# FanPump.net
KiCad netlist of a schematic drawn in Altium Designer
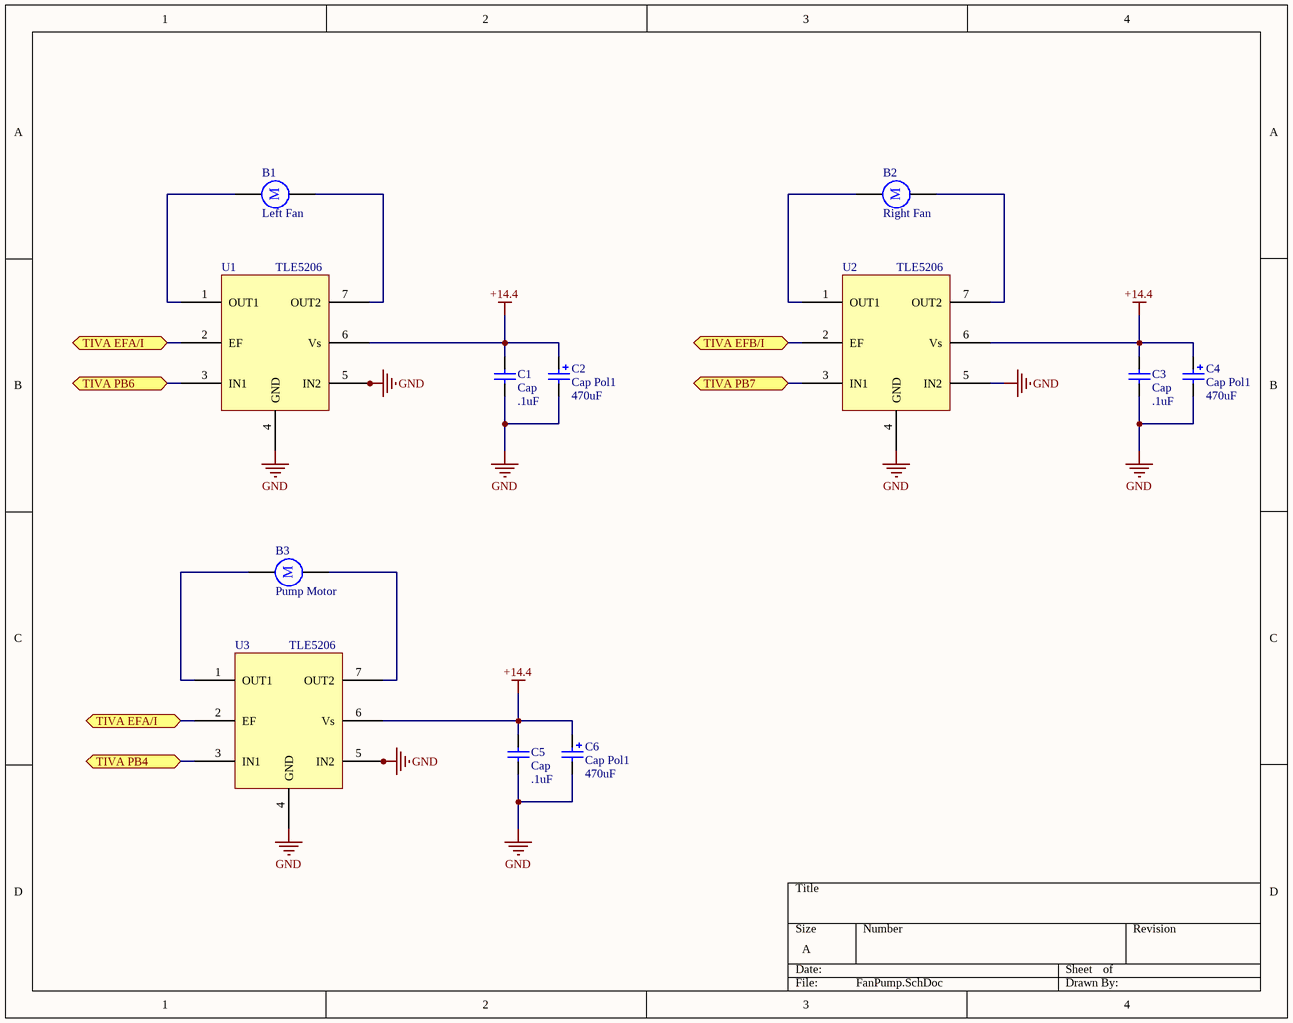
[diagram p0: FanPump.SchDoc]

(export (version "E")
  (design (tool "Eeschema 10.0.6"))
  (components
    (comp (ref "B1")
      (value "Left Fan")
      (footprint "RB5-10.5")
      (description "Motor, General Kind")
      (fields (field (name "MANUFACTURER") "Generic Components"))
      (libsource (lib "ME218_BaseLib") (part "Motor"))
    )
    (comp (ref "B2")
      (value "Right Fan")
      (footprint "RB5-10.5")
      (description "Motor, General Kind")
      (fields (field (name "MANUFACTURER") "Generic Components"))
      (libsource (lib "ME218_BaseLib") (part "Motor"))
    )
    (comp (ref "B3")
      (value "Pump Motor")
      (footprint "RB5-10.5")
      (description "Motor, General Kind")
      (fields (field (name "MANUFACTURER") "Generic Components"))
      (libsource (lib "ME218_BaseLib") (part "Motor"))
    )
    (comp (ref "C1")
      (value "Cap")
      (footprint "RAD-0.3")
      (description "Capacitor")
      (fields
        (field (name "MANUFACTURER") "Generic Components")
        (field (name "ALTIUM_VALUE") ".1uF")
        (field (name "PUBLISHER") "Altium Hobart Technology Centre")
      )
      (libsource (lib "ME218_BaseLib") (part "Cap"))
    )
    (comp (ref "C2")
      (value "Cap Pol1")
      (footprint "RB7.6-15")
      (description "Polarized Capacitor (Radial)")
      (fields
        (field (name "MANUFACTURER") "Generic Components")
        (field (name "ALTIUM_VALUE") "470uF")
        (field (name "PUBLISHER") "Altium Hobart Technology Centre")
      )
      (libsource (lib "ME218_BaseLib") (part "Cap Pol1"))
    )
    (comp (ref "C3")
      (value "Cap")
      (footprint "RAD-0.3")
      (description "Capacitor")
      (fields
        (field (name "MANUFACTURER") "Generic Components")
        (field (name "ALTIUM_VALUE") ".1uF")
        (field (name "PUBLISHER") "Altium Hobart Technology Centre")
      )
      (libsource (lib "ME218_BaseLib") (part "Cap"))
    )
    (comp (ref "C4")
      (value "Cap Pol1")
      (footprint "RB7.6-15")
      (description "Polarized Capacitor (Radial)")
      (fields
        (field (name "MANUFACTURER") "Generic Components")
        (field (name "ALTIUM_VALUE") "470uF")
        (field (name "PUBLISHER") "Altium Hobart Technology Centre")
      )
      (libsource (lib "ME218_BaseLib") (part "Cap Pol1"))
    )
    (comp (ref "C5")
      (value "Cap")
      (footprint "RAD-0.3")
      (description "Capacitor")
      (fields
        (field (name "MANUFACTURER") "Generic Components")
        (field (name "ALTIUM_VALUE") ".1uF")
        (field (name "PUBLISHER") "Altium Hobart Technology Centre")
      )
      (libsource (lib "ME218_BaseLib") (part "Cap"))
    )
    (comp (ref "C6")
      (value "Cap Pol1")
      (footprint "RB7.6-15")
      (description "Polarized Capacitor (Radial)")
      (fields
        (field (name "MANUFACTURER") "Generic Components")
        (field (name "ALTIUM_VALUE") "470uF")
        (field (name "PUBLISHER") "Altium Hobart Technology Centre")
      )
      (libsource (lib "ME218_BaseLib") (part "Cap Pol1"))
    )
    (comp (ref "U1") (value "TLE5206") (libsource (lib "ProjectLib") (part "TLE5206")))
    (comp (ref "U2") (value "TLE5206") (libsource (lib "ProjectLib") (part "TLE5206")))
    (comp (ref "U3") (value "TLE5206") (libsource (lib "ProjectLib") (part "TLE5206")))
  )
  (nets
    (net (code "1") (name "+14.4") (class "Default")
      (node (ref "C1") (pin "2") (pinfunction "2_2") (pintype "passive"))
      (node (ref "C2") (pin "1") (pinfunction "1_1") (pintype "passive"))
      (node (ref "C3") (pin "2") (pinfunction "2_2") (pintype "passive"))
      (node (ref "C4") (pin "1") (pinfunction "1_1") (pintype "passive"))
      (node (ref "C5") (pin "2") (pinfunction "2_2") (pintype "passive"))
      (node (ref "C6") (pin "1") (pinfunction "1_1") (pintype "passive"))
      (node (ref "U1") (pin "6") (pinfunction "Vs_6") (pintype "passive"))
      (node (ref "U2") (pin "6") (pinfunction "Vs_6") (pintype "passive"))
      (node (ref "U3") (pin "6") (pinfunction "Vs_6") (pintype "passive"))
    )
    (net (code "2") (name "/TIVA EFA{slash}I") (class "Default")
      (node (ref "U1") (pin "2") (pinfunction "EF_2") (pintype "passive"))
      (node (ref "U3") (pin "2") (pinfunction "EF_2") (pintype "passive"))
    )
    (net (code "3") (name "/TIVA EFB{slash}I") (class "Default")
      (node (ref "U2") (pin "2") (pinfunction "EF_2") (pintype "passive"))
    )
    (net (code "4") (name "/TIVA PB4") (class "Default")
      (node (ref "U3") (pin "3") (pinfunction "IN1_3") (pintype "passive"))
    )
    (net (code "5") (name "/TIVA PB6") (class "Default")
      (node (ref "U1") (pin "3") (pinfunction "IN1_3") (pintype "passive"))
    )
    (net (code "6") (name "/TIVA PB7") (class "Default")
      (node (ref "U2") (pin "3") (pinfunction "IN1_3") (pintype "passive"))
    )
    (net (code "7") (name "GND") (class "Default")
      (node (ref "C1") (pin "1") (pinfunction "1_1") (pintype "passive"))
      (node (ref "C2") (pin "2") (pinfunction "2_2") (pintype "passive"))
      (node (ref "C3") (pin "1") (pinfunction "1_1") (pintype "passive"))
      (node (ref "C4") (pin "2") (pinfunction "2_2") (pintype "passive"))
      (node (ref "C5") (pin "1") (pinfunction "1_1") (pintype "passive"))
      (node (ref "C6") (pin "2") (pinfunction "2_2") (pintype "passive"))
      (node (ref "U1") (pin "4") (pinfunction "GND_4") (pintype "passive"))
      (node (ref "U1") (pin "5") (pinfunction "IN2_5") (pintype "passive"))
      (node (ref "U2") (pin "4") (pinfunction "GND_4") (pintype "passive"))
      (node (ref "U2") (pin "5") (pinfunction "IN2_5") (pintype "passive"))
      (node (ref "U3") (pin "4") (pinfunction "GND_4") (pintype "passive"))
      (node (ref "U3") (pin "5") (pinfunction "IN2_5") (pintype "passive"))
    )
    (net (code "8") (name "Net-(U1-OUT1)") (class "Default")
      (node (ref "B1") (pin "1") (pinfunction "1_1") (pintype "passive"))
      (node (ref "U1") (pin "1") (pinfunction "OUT1_1") (pintype "passive"))
    )
    (net (code "9") (name "Net-(U1-OUT2)") (class "Default")
      (node (ref "B1") (pin "2") (pinfunction "2_2") (pintype "passive"))
      (node (ref "U1") (pin "7") (pinfunction "OUT2_7") (pintype "passive"))
    )
    (net (code "10") (name "Net-(U2-OUT1)") (class "Default")
      (node (ref "B2") (pin "1") (pinfunction "1_1") (pintype "passive"))
      (node (ref "U2") (pin "1") (pinfunction "OUT1_1") (pintype "passive"))
    )
    (net (code "11") (name "Net-(U2-OUT2)") (class "Default")
      (node (ref "B2") (pin "2") (pinfunction "2_2") (pintype "passive"))
      (node (ref "U2") (pin "7") (pinfunction "OUT2_7") (pintype "passive"))
    )
    (net (code "12") (name "Net-(U3-OUT1)") (class "Default")
      (node (ref "B3") (pin "1") (pinfunction "1_1") (pintype "passive"))
      (node (ref "U3") (pin "1") (pinfunction "OUT1_1") (pintype "passive"))
    )
    (net (code "13") (name "Net-(U3-OUT2)") (class "Default")
      (node (ref "B3") (pin "2") (pinfunction "2_2") (pintype "passive"))
      (node (ref "U3") (pin "7") (pinfunction "OUT2_7") (pintype "passive"))
    )
  )
)
